# PCIE_CLK.net
KiCad netlist of a schematic drawn in Altium Designer
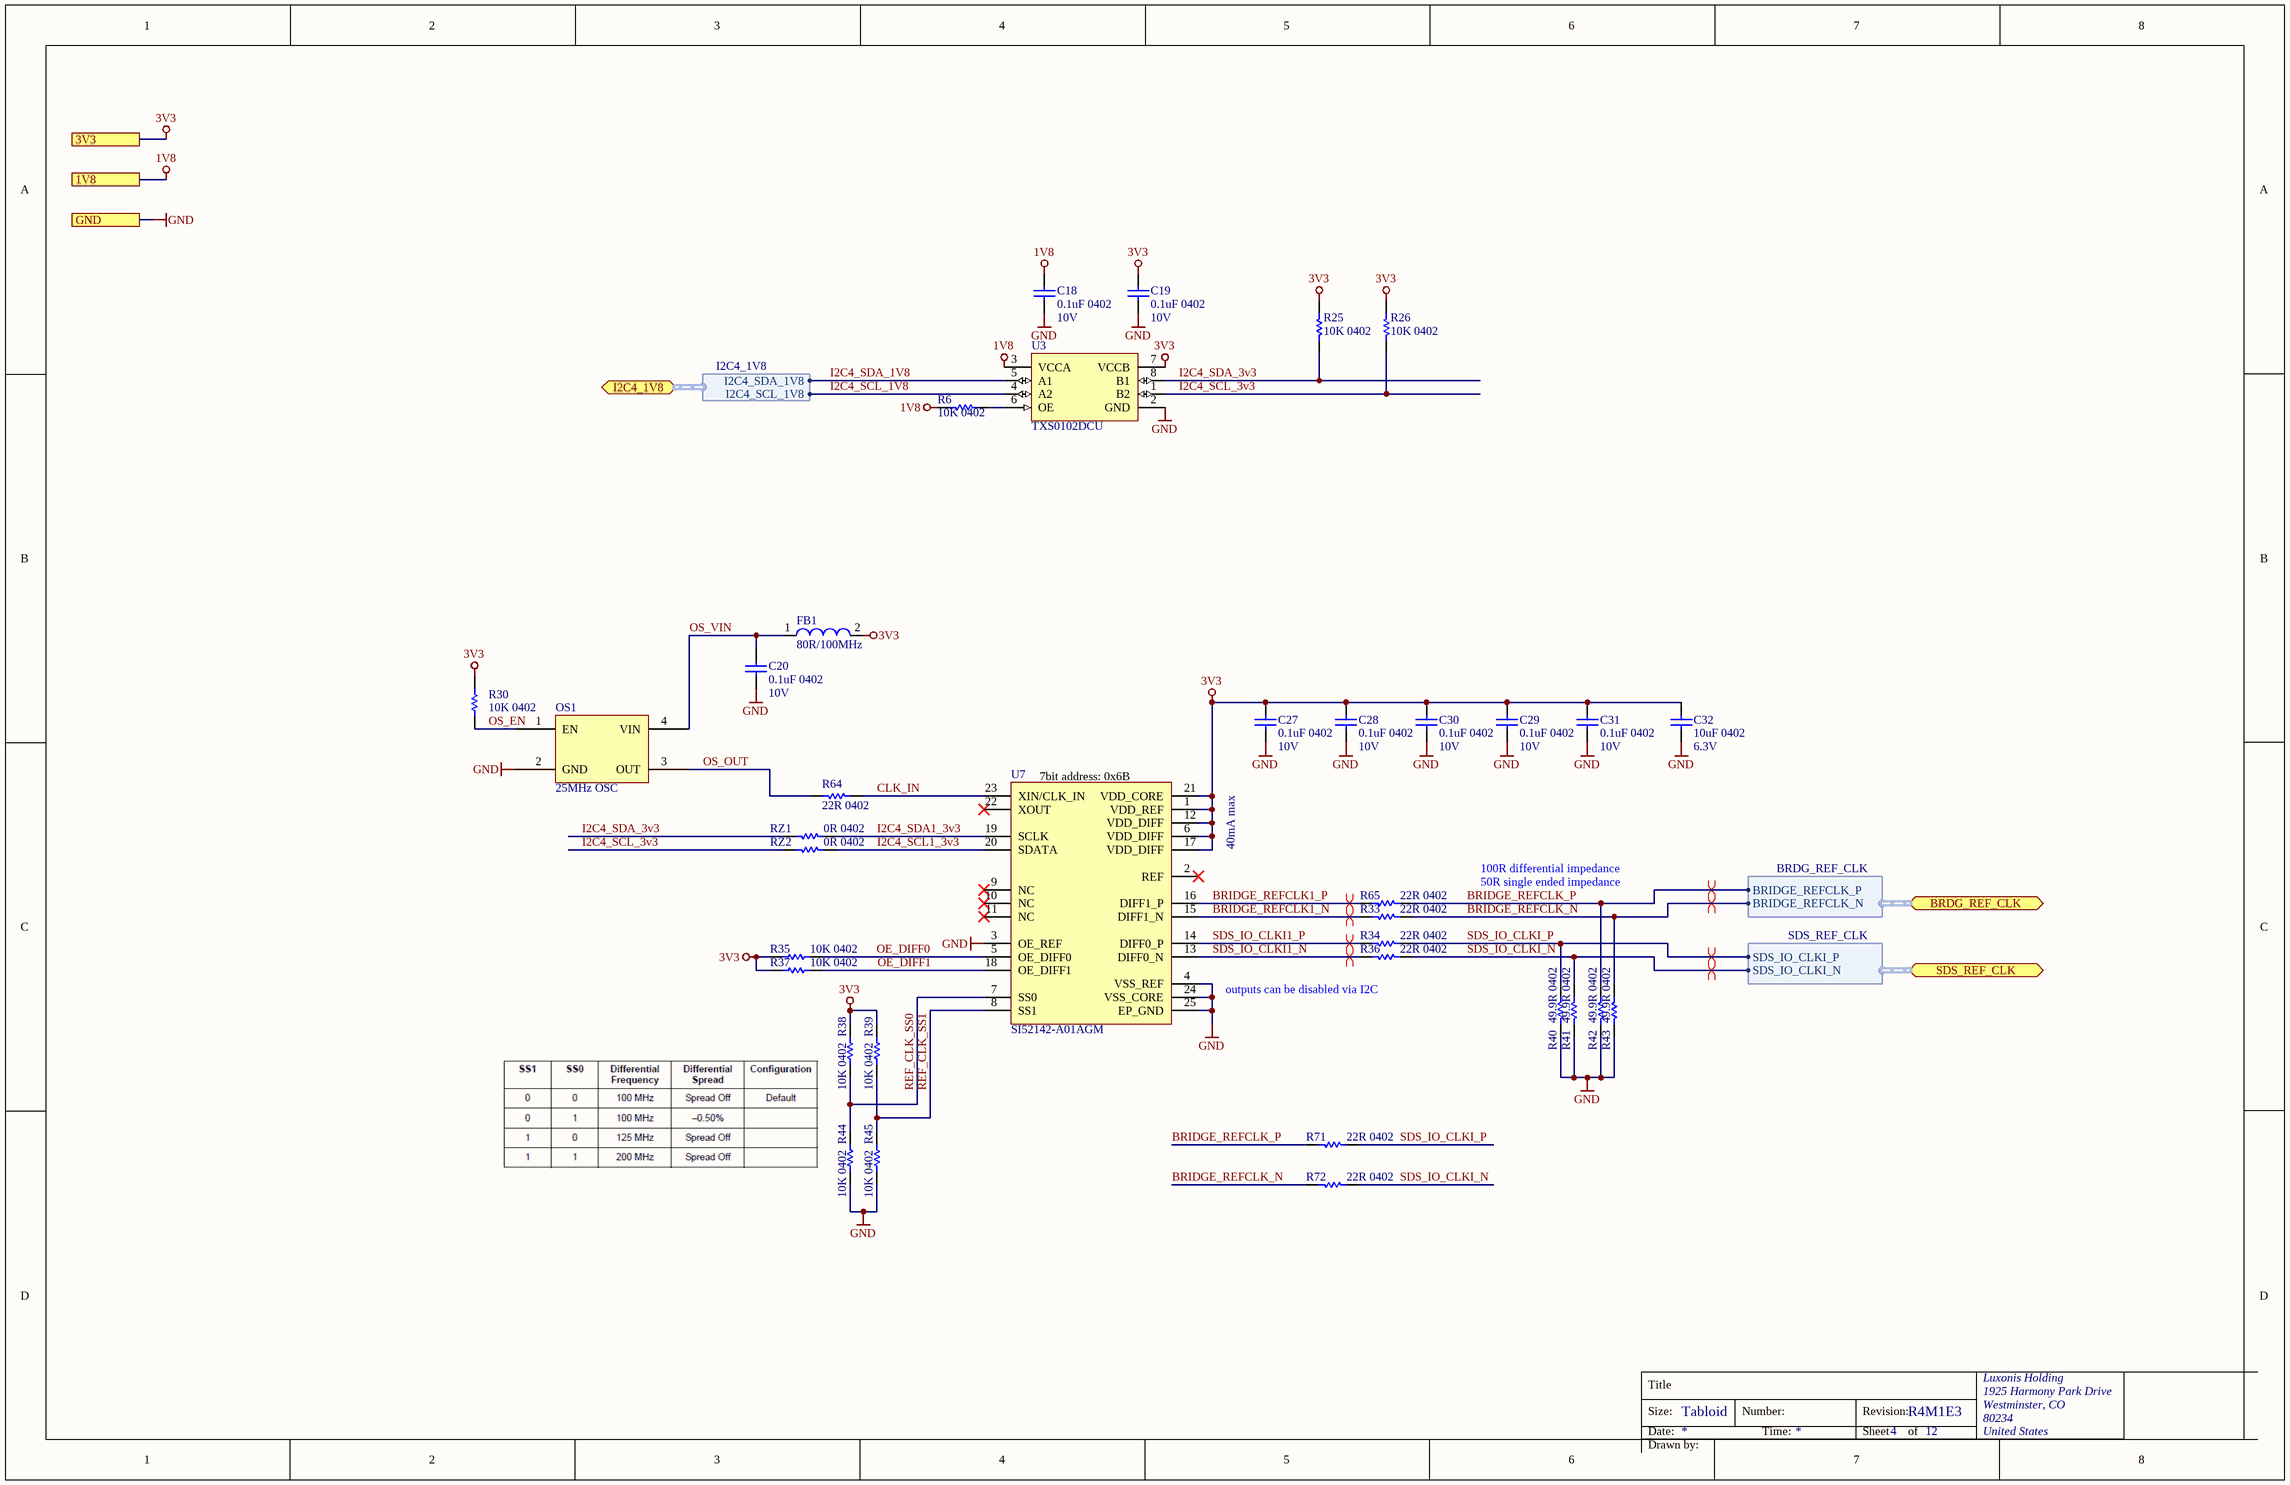
[diagram p0: PCIE_CLK.SchDoc]

(export (version "E")
  (design (tool "Eeschema 10.0.6"))
  (components
    (comp (ref "C18")
      (value "0.1uF 0402")
      (footprint "CAP_Altium_Vault_Generic:CAPC0402(1005)70_N")
      (description "CAP CER 0.1UF 10V X7R 0402 5%")
      (fields (field (name "TOLERANCE") "5%") (field (name "VOLTAGE RATING") "10V"))
      (libsource (lib "LuxonisMaster") (part "GRM155R71A104JA01D"))
    )
    (comp (ref "C19")
      (value "0.1uF 0402")
      (footprint "CAP_Altium_Vault_Generic:CAPC0402(1005)70_N")
      (description "CAP CER 0.1UF 10V X7R 0402 5%")
      (fields (field (name "TOLERANCE") "5%") (field (name "VOLTAGE RATING") "10V"))
      (libsource (lib "LuxonisMaster") (part "GRM155R71A104JA01D"))
    )
    (comp (ref "C20")
      (value "0.1uF 0402")
      (footprint "CAP_Altium_Vault_Generic:CAPC0402(1005)70_N")
      (description "CAP CER 0.1UF 10V X7R 0402 5%")
      (fields (field (name "TOLERANCE") "5%") (field (name "VOLTAGE RATING") "10V"))
      (libsource (lib "LuxonisMaster") (part "GRM155R71A104JA01D"))
    )
    (comp (ref "C27")
      (value "0.1uF 0402")
      (footprint "CAP_Altium_Vault_Generic:CAPC0402(1005)70_N")
      (description "CAP CER 0.1UF 10V X7R 0402 5%")
      (fields (field (name "TOLERANCE") "5%") (field (name "VOLTAGE RATING") "10V"))
      (libsource (lib "LuxonisMaster") (part "GRM155R71A104JA01D"))
    )
    (comp (ref "C28")
      (value "0.1uF 0402")
      (footprint "CAP_Altium_Vault_Generic:CAPC0402(1005)70_N")
      (description "CAP CER 0.1UF 10V X7R 0402 5%")
      (fields (field (name "TOLERANCE") "5%") (field (name "VOLTAGE RATING") "10V"))
      (libsource (lib "LuxonisMaster") (part "GRM155R71A104JA01D"))
    )
    (comp (ref "C29")
      (value "0.1uF 0402")
      (footprint "CAP_Altium_Vault_Generic:CAPC0402(1005)70_N")
      (description "CAP CER 0.1UF 10V X7R 0402 5%")
      (fields (field (name "TOLERANCE") "5%") (field (name "VOLTAGE RATING") "10V"))
      (libsource (lib "LuxonisMaster") (part "GRM155R71A104JA01D"))
    )
    (comp (ref "C30")
      (value "0.1uF 0402")
      (footprint "CAP_Altium_Vault_Generic:CAPC0402(1005)70_N")
      (description "CAP CER 0.1UF 10V X7R 0402 5%")
      (fields (field (name "TOLERANCE") "5%") (field (name "VOLTAGE RATING") "10V"))
      (libsource (lib "LuxonisMaster") (part "GRM155R71A104JA01D"))
    )
    (comp (ref "C31")
      (value "0.1uF 0402")
      (footprint "CAP_Altium_Vault_Generic:CAPC0402(1005)70_N")
      (description "CAP CER 0.1UF 10V X7R 0402 5%")
      (fields (field (name "TOLERANCE") "5%") (field (name "VOLTAGE RATING") "10V"))
      (libsource (lib "LuxonisMaster") (part "GRM155R71A104JA01D"))
    )
    (comp (ref "C32")
      (value "10uF 0402")
      (footprint "CAP_Altium_Vault_Generic:CAPC0402(1005)70_N")
      (description "CAP CER 10UF 6.3V X5R 0402 20%")
      (fields (field (name "TOLERANCE") "20%") (field (name "VOLTAGE RATING") "6.3V"))
      (libsource (lib "LuxonisMaster") (part "GRM155R60J106ME15D"))
    )
    (comp (ref "FB1")
      (value "80R/100MHz")
      (footprint "LuxonisMaster:BK1608HS800-T_N")
      (description "FERRITE BEAD 80 OHM 0603 1LN")
      (fields (field (name "TOLERANCE") "25%"))
      (libsource (lib "LuxonisMaster") (part "BK1608HS800-T"))
    )
    (comp (ref "OS1")
      (value "25MHz OSC")
      (footprint "BW2098POE:ASDMB-25.000MHZ-LC-T")
      (description "MEMS OSC XO 25.0000MHZ LVCMOS")
      (libsource (lib "BW2098POE") (part "ASDMB-25.000MHZ-LC-T"))
    )
    (comp (ref "R6")
      (value "10K 0402")
      (footprint "RES_Altium_Vault_Generic:RESC0402(1005)_N")
      (fields (field (name "TOLERANCE") "1%"))
      (libsource (lib "LuxonisMaster") (part "RC0402FR-1310KL"))
    )
    (comp (ref "R25")
      (value "10K 0402")
      (footprint "RES_Altium_Vault_Generic:RESC0402(1005)_N")
      (fields (field (name "TOLERANCE") "1%"))
      (libsource (lib "LuxonisMaster") (part "RC0402FR-1310KL"))
    )
    (comp (ref "R26")
      (value "10K 0402")
      (footprint "RES_Altium_Vault_Generic:RESC0402(1005)_N")
      (fields (field (name "TOLERANCE") "1%"))
      (libsource (lib "LuxonisMaster") (part "RC0402FR-1310KL"))
    )
    (comp (ref "R30")
      (value "10K 0402")
      (footprint "RES_Altium_Vault_Generic:RESC0402(1005)_N")
      (fields (field (name "TOLERANCE") "1%"))
      (libsource (lib "LuxonisMaster") (part "RC0402FR-1310KL"))
    )
    (comp (ref "R33")
      (value "22R 0402")
      (footprint "RES_Altium_Vault_Generic:RESC0402(1005)_L")
      (description "RES SMD 22 OHM 1% 1/16W 0402")
      (fields (field (name "TOLERANCE") "1%"))
      (libsource (lib "BW2098POE") (part "RC0402FR-0722RL"))
    )
    (comp (ref "R34")
      (value "22R 0402")
      (footprint "RES_Altium_Vault_Generic:RESC0402(1005)_L")
      (description "RES SMD 22 OHM 1% 1/16W 0402")
      (fields (field (name "TOLERANCE") "1%"))
      (libsource (lib "BW2098POE") (part "RC0402FR-0722RL"))
    )
    (comp (ref "R35")
      (value "10K 0402")
      (footprint "RES_Altium_Vault_Generic:RESC0402(1005)_N")
      (fields (field (name "TOLERANCE") "1%"))
      (libsource (lib "LuxonisMaster") (part "RC0402FR-1310KL"))
    )
    (comp (ref "R36")
      (value "22R 0402")
      (footprint "RES_Altium_Vault_Generic:RESC0402(1005)_L")
      (description "RES SMD 22 OHM 1% 1/16W 0402")
      (fields (field (name "TOLERANCE") "1%"))
      (libsource (lib "BW2098POE") (part "RC0402FR-0722RL"))
    )
    (comp (ref "R37")
      (value "10K 0402")
      (footprint "RES_Altium_Vault_Generic:RESC0402(1005)_N")
      (fields (field (name "TOLERANCE") "1%"))
      (libsource (lib "LuxonisMaster") (part "RC0402FR-1310KL"))
    )
    (comp (ref "R38")
      (value "10K 0402")
      (footprint "RES_Altium_Vault_Generic:RESC0402(1005)_N")
      (fields (field (name "TOLERANCE") "1%"))
      (libsource (lib "LuxonisMaster") (part "RC0402FR-1310KL"))
    )
    (comp (ref "R39")
      (value "10K 0402")
      (footprint "RES_Altium_Vault_Generic:RESC0402(1005)_N")
      (fields (field (name "TOLERANCE") "1%"))
      (libsource (lib "LuxonisMaster") (part "RC0402FR-1310KL"))
    )
    (comp (ref "R40")
      (value "49.9R 0402")
      (footprint "RES_Altium_Vault_Generic:RESC0402(1005)_L")
      (description "RES SMD 49.9 OHM 1% 1/16W 0402")
      (fields (field (name "TOLERANCE") "1%"))
      (libsource (lib "LuxonisMaster") (part "RC0402FR-0749R9L"))
    )
    (comp (ref "R41")
      (value "49.9R 0402")
      (footprint "RES_Altium_Vault_Generic:RESC0402(1005)_L")
      (description "RES SMD 49.9 OHM 1% 1/16W 0402")
      (fields (field (name "TOLERANCE") "1%"))
      (libsource (lib "LuxonisMaster") (part "RC0402FR-0749R9L"))
    )
    (comp (ref "R42")
      (value "49.9R 0402")
      (footprint "RES_Altium_Vault_Generic:RESC0402(1005)_L")
      (description "RES SMD 49.9 OHM 1% 1/16W 0402")
      (fields (field (name "TOLERANCE") "1%"))
      (libsource (lib "LuxonisMaster") (part "RC0402FR-0749R9L"))
    )
    (comp (ref "R43")
      (value "49.9R 0402")
      (footprint "RES_Altium_Vault_Generic:RESC0402(1005)_L")
      (description "RES SMD 49.9 OHM 1% 1/16W 0402")
      (fields (field (name "TOLERANCE") "1%"))
      (libsource (lib "LuxonisMaster") (part "RC0402FR-0749R9L"))
    )
    (comp (ref "R44")
      (value "10K 0402")
      (footprint "RES_Altium_Vault_Generic:RESC0402(1005)_N")
      (fields (field (name "TOLERANCE") "1%"))
      (libsource (lib "LuxonisMaster") (part "RC0402FR-1310KL"))
    )
    (comp (ref "R45")
      (value "10K 0402")
      (footprint "RES_Altium_Vault_Generic:RESC0402(1005)_N")
      (fields (field (name "TOLERANCE") "1%"))
      (libsource (lib "LuxonisMaster") (part "RC0402FR-1310KL"))
    )
    (comp (ref "R64")
      (value "22R 0402")
      (footprint "RES_Altium_Vault_Generic:RESC0402(1005)_N")
      (description "RES SMD 22 OHM 1% 1/16W 0402")
      (fields (field (name "TOLERANCE") "1%"))
      (libsource (lib "BW2098POE") (part "RC0402FR-0722RL"))
    )
    (comp (ref "R65")
      (value "22R 0402")
      (footprint "RES_Altium_Vault_Generic:RESC0402(1005)_L")
      (description "RES SMD 22 OHM 1% 1/16W 0402")
      (fields (field (name "TOLERANCE") "1%"))
      (libsource (lib "BW2098POE") (part "RC0402FR-0722RL"))
    )
    (comp (ref "R71")
      (value "22R 0402")
      (footprint "RES_Altium_Vault_Generic:RESC0402(1005)_L")
      (description "RES SMD 22 OHM 1% 1/16W 0402")
      (fields (field (name "TOLERANCE") "1%"))
      (libsource (lib "BW2098POE") (part "RC0402FR-0722RL"))
    )
    (comp (ref "R72")
      (value "22R 0402")
      (footprint "RES_Altium_Vault_Generic:RESC0402(1005)_L")
      (description "RES SMD 22 OHM 1% 1/16W 0402")
      (fields (field (name "TOLERANCE") "1%"))
      (libsource (lib "BW2098POE") (part "RC0402FR-0722RL"))
    )
    (comp (ref "RZ1")
      (value "0R 0402")
      (footprint "RES_Altium_Vault_Generic:RESC0402(1005)_N")
      (description "RES SMD 0 OHM JUMPER 1/16W 0402")
      (fields (field (name "TOLERANCE") "5%"))
      (libsource (lib "LuxonisMaster") (part "CRCW04020000Z0ED"))
    )
    (comp (ref "RZ2")
      (value "0R 0402")
      (footprint "RES_Altium_Vault_Generic:RESC0402(1005)_N")
      (description "RES SMD 0 OHM JUMPER 1/16W 0402")
      (fields (field (name "TOLERANCE") "5%"))
      (libsource (lib "LuxonisMaster") (part "CRCW04020000Z0ED"))
    )
    (comp (ref "U3")
      (value "TXS0102DCU")
      (footprint "BW2098POE:TXS0102DCUR")
      (description "TEXAS INSTRUMENTS - TXS0102DCUR - IC, TRANSLATOR, 2 BIT, BI, US-8")
      (libsource (lib "BW2098POE") (part "TXS0102DCUR"))
    )
    (comp (ref "U7")
      (value "SI52142-A01AGM")
      (footprint "BW2098POE:SI52142-A01AGM")
      (description "IC CLK GENERATOR 200MHZ 24QFN")
      (libsource (lib "BW2098POE") (part "SI52142-A01AGM"))
    )
  )
  (nets
    (net (code "4") (name "/BRIDGE_REFCLK1_N") (class "Default")
      (node (ref "R33") (pin "2") (pinfunction "2_2") (pintype "passive"))
      (node (ref "U7") (pin "15") (pinfunction "DIFF1_N_15") (pintype "passive"))
    )
    (net (code "5") (name "/BRIDGE_REFCLK1_P") (class "Default")
      (node (ref "R65") (pin "2") (pinfunction "2_2") (pintype "passive"))
      (node (ref "U7") (pin "16") (pinfunction "DIFF1_P_16") (pintype "passive"))
    )
    (net (code "6") (name "/BRIDGE_REFCLK_N") (class "Default")
      (node (ref "R33") (pin "1") (pinfunction "1_1") (pintype "passive"))
      (node (ref "R43") (pin "2") (pinfunction "2_2") (pintype "passive"))
      (node (ref "R72") (pin "2") (pinfunction "2_2") (pintype "passive"))
    )
    (net (code "7") (name "/BRIDGE_REFCLK_P") (class "Default")
      (node (ref "R42") (pin "2") (pinfunction "2_2") (pintype "passive"))
      (node (ref "R65") (pin "1") (pinfunction "1_1") (pintype "passive"))
      (node (ref "R71") (pin "2") (pinfunction "2_2") (pintype "passive"))
    )
    (net (code "8") (name "/CLK_IN") (class "Default")
      (node (ref "R64") (pin "1") (pinfunction "1_1") (pintype "passive"))
      (node (ref "U7") (pin "23") (pinfunction "XIN/CLK_IN_23") (pintype "passive"))
    )
    (net (code "9") (name "/I2C4_SCL1_3v3") (class "Default")
      (node (ref "RZ2") (pin "2") (pinfunction "2_2") (pintype "passive"))
      (node (ref "U7") (pin "20") (pinfunction "SDATA_20") (pintype "passive"))
    )
    (net (code "10") (name "/I2C4_SCL_1V8") (class "Default")
      (node (ref "U3") (pin "4") (pinfunction "A2_4") (pintype "bidirectional"))
    )
    (net (code "11") (name "/I2C4_SCL_3v3") (class "Default")
      (node (ref "R26") (pin "2") (pinfunction "2_2") (pintype "passive"))
      (node (ref "RZ2") (pin "1") (pinfunction "1_1") (pintype "passive"))
      (node (ref "U3") (pin "1") (pinfunction "B2_1") (pintype "bidirectional"))
    )
    (net (code "12") (name "/I2C4_SDA1_3v3") (class "Default")
      (node (ref "RZ1") (pin "2") (pinfunction "2_2") (pintype "passive"))
      (node (ref "U7") (pin "19") (pinfunction "SCLK_19") (pintype "passive"))
    )
    (net (code "13") (name "/I2C4_SDA_1V8") (class "Default")
      (node (ref "U3") (pin "5") (pinfunction "A1_5") (pintype "bidirectional"))
    )
    (net (code "14") (name "/I2C4_SDA_3v3") (class "Default")
      (node (ref "R25") (pin "2") (pinfunction "2_2") (pintype "passive"))
      (node (ref "RZ1") (pin "1") (pinfunction "1_1") (pintype "passive"))
      (node (ref "U3") (pin "8") (pinfunction "B1_8") (pintype "bidirectional"))
    )
    (net (code "15") (name "/OE_DIFF0") (class "Default")
      (node (ref "R35") (pin "2") (pinfunction "2_2") (pintype "passive"))
      (node (ref "U7") (pin "5") (pinfunction "OE_DIFF0_5") (pintype "passive"))
    )
    (net (code "16") (name "/OE_DIFF1") (class "Default")
      (node (ref "R37") (pin "2") (pinfunction "2_2") (pintype "passive"))
      (node (ref "U7") (pin "18") (pinfunction "OE_DIFF1_18") (pintype "passive"))
    )
    (net (code "17") (name "/OS_EN") (class "Default")
      (node (ref "OS1") (pin "1") (pinfunction "EN_1") (pintype "passive"))
      (node (ref "R30") (pin "1") (pinfunction "1_1") (pintype "passive"))
    )
    (net (code "18") (name "/OS_OUT") (class "Default")
      (node (ref "OS1") (pin "3") (pinfunction "OUT_3") (pintype "passive"))
      (node (ref "R64") (pin "2") (pinfunction "2_2") (pintype "passive"))
    )
    (net (code "19") (name "/OS_VIN") (class "Default")
      (node (ref "C20") (pin "1") (pinfunction "1_1") (pintype "passive"))
      (node (ref "FB1") (pin "1") (pinfunction "1_1") (pintype "passive"))
      (node (ref "OS1") (pin "4") (pinfunction "VIN_4") (pintype "passive"))
    )
    (net (code "20") (name "/REF_CLK_SS0") (class "Default")
      (node (ref "R38") (pin "2") (pinfunction "2_2") (pintype "passive"))
      (node (ref "R44") (pin "1") (pinfunction "1_1") (pintype "passive"))
      (node (ref "U7") (pin "7") (pinfunction "SS0_7") (pintype "passive"))
    )
    (net (code "21") (name "/REF_CLK_SS1") (class "Default")
      (node (ref "R39") (pin "2") (pinfunction "2_2") (pintype "passive"))
      (node (ref "R45") (pin "1") (pinfunction "1_1") (pintype "passive"))
      (node (ref "U7") (pin "8") (pinfunction "SS1_8") (pintype "passive"))
    )
    (net (code "22") (name "/SDS_IO_CLKI1_N") (class "Default")
      (node (ref "R36") (pin "2") (pinfunction "2_2") (pintype "passive"))
      (node (ref "U7") (pin "13") (pinfunction "DIFF0_N_13") (pintype "passive"))
    )
    (net (code "23") (name "/SDS_IO_CLKI1_P") (class "Default")
      (node (ref "R34") (pin "2") (pinfunction "2_2") (pintype "passive"))
      (node (ref "U7") (pin "14") (pinfunction "DIFF0_P_14") (pintype "passive"))
    )
    (net (code "24") (name "/SDS_IO_CLKI_N") (class "Default")
      (node (ref "R36") (pin "1") (pinfunction "1_1") (pintype "passive"))
      (node (ref "R41") (pin "2") (pinfunction "2_2") (pintype "passive"))
      (node (ref "R72") (pin "1") (pinfunction "1_1") (pintype "passive"))
    )
    (net (code "25") (name "/SDS_IO_CLKI_P") (class "Default")
      (node (ref "R34") (pin "1") (pinfunction "1_1") (pintype "passive"))
      (node (ref "R40") (pin "1") (pinfunction "1_1") (pintype "passive"))
      (node (ref "R71") (pin "1") (pinfunction "1_1") (pintype "passive"))
    )
    (net (code "29") (name "1V8") (class "Default")
      (node (ref "C18") (pin "2") (pinfunction "2_2") (pintype "passive"))
      (node (ref "R6") (pin "2") (pinfunction "2_2") (pintype "passive"))
      (node (ref "U3") (pin "3") (pinfunction "VCCA_3") (pintype "power_in"))
    )
    (net (code "30") (name "3V3") (class "Default")
      (node (ref "C19") (pin "2") (pinfunction "2_2") (pintype "passive"))
      (node (ref "C27") (pin "1") (pinfunction "1_1") (pintype "passive"))
      (node (ref "C28") (pin "1") (pinfunction "1_1") (pintype "passive"))
      (node (ref "C29") (pin "1") (pinfunction "1_1") (pintype "passive"))
      (node (ref "C30") (pin "1") (pinfunction "1_1") (pintype "passive"))
      (node (ref "C31") (pin "1") (pinfunction "1_1") (pintype "passive"))
      (node (ref "C32") (pin "2") (pinfunction "2_2") (pintype "passive"))
      (node (ref "FB1") (pin "2") (pinfunction "2_2") (pintype "passive"))
      (node (ref "R25") (pin "1") (pinfunction "1_1") (pintype "passive"))
      (node (ref "R26") (pin "1") (pinfunction "1_1") (pintype "passive"))
      (node (ref "R30") (pin "2") (pinfunction "2_2") (pintype "passive"))
      (node (ref "R35") (pin "1") (pinfunction "1_1") (pintype "passive"))
      (node (ref "R37") (pin "1") (pinfunction "1_1") (pintype "passive"))
      (node (ref "R38") (pin "1") (pinfunction "1_1") (pintype "passive"))
      (node (ref "R39") (pin "1") (pinfunction "1_1") (pintype "passive"))
      (node (ref "U3") (pin "7") (pinfunction "VCCB_7") (pintype "power_in"))
      (node (ref "U7") (pin "1") (pinfunction "VDD_REF_1") (pintype "passive"))
      (node (ref "U7") (pin "12") (pinfunction "VDD_DIFF_12") (pintype "passive"))
      (node (ref "U7") (pin "17") (pinfunction "VDD_DIFF_17") (pintype "passive"))
      (node (ref "U7") (pin "21") (pinfunction "VDD_CORE_21") (pintype "passive"))
      (node (ref "U7") (pin "6") (pinfunction "VDD_DIFF_6") (pintype "passive"))
    )
    (net (code "31") (name "GND") (class "Default")
      (node (ref "C18") (pin "1") (pinfunction "1_1") (pintype "passive"))
      (node (ref "C19") (pin "1") (pinfunction "1_1") (pintype "passive"))
      (node (ref "C20") (pin "2") (pinfunction "2_2") (pintype "passive"))
      (node (ref "C27") (pin "2") (pinfunction "2_2") (pintype "passive"))
      (node (ref "C28") (pin "2") (pinfunction "2_2") (pintype "passive"))
      (node (ref "C29") (pin "2") (pinfunction "2_2") (pintype "passive"))
      (node (ref "C30") (pin "2") (pinfunction "2_2") (pintype "passive"))
      (node (ref "C31") (pin "2") (pinfunction "2_2") (pintype "passive"))
      (node (ref "C32") (pin "1") (pinfunction "1_1") (pintype "passive"))
      (node (ref "OS1") (pin "2") (pinfunction "GND_2") (pintype "passive"))
      (node (ref "R40") (pin "2") (pinfunction "2_2") (pintype "passive"))
      (node (ref "R41") (pin "1") (pinfunction "1_1") (pintype "passive"))
      (node (ref "R42") (pin "1") (pinfunction "1_1") (pintype "passive"))
      (node (ref "R43") (pin "1") (pinfunction "1_1") (pintype "passive"))
      (node (ref "R44") (pin "2") (pinfunction "2_2") (pintype "passive"))
      (node (ref "R45") (pin "2") (pinfunction "2_2") (pintype "passive"))
      (node (ref "U3") (pin "2") (pinfunction "GND_2") (pintype "power_in"))
      (node (ref "U7") (pin "24") (pinfunction "VSS_CORE_24") (pintype "passive"))
      (node (ref "U7") (pin "25") (pinfunction "EP_GND_25") (pintype "passive"))
      (node (ref "U7") (pin "3") (pinfunction "OE_REF_3") (pintype "passive"))
      (node (ref "U7") (pin "4") (pinfunction "VSS_REF_4") (pintype "passive"))
    )
    (net (code "32") (name "Net-(U3-OE)") (class "Default")
      (node (ref "R6") (pin "1") (pinfunction "1_1") (pintype "passive"))
      (node (ref "U3") (pin "6") (pinfunction "OE_6") (pintype "input"))
    )
    (net (code "33") (name "unconnected-(U7-NC-Pad9)") (class "Default")
      (node (ref "U7") (pin "9") (pinfunction "NC_9") (pintype "passive+no_connect"))
    )
    (net (code "34") (name "unconnected-(U7-NC-Pad10)") (class "Default")
      (node (ref "U7") (pin "10") (pinfunction "NC_10") (pintype "passive+no_connect"))
    )
    (net (code "35") (name "unconnected-(U7-NC-Pad11)") (class "Default")
      (node (ref "U7") (pin "11") (pinfunction "NC_11") (pintype "passive+no_connect"))
    )
    (net (code "36") (name "unconnected-(U7-REF-Pad2)") (class "Default")
      (node (ref "U7") (pin "2") (pinfunction "REF_2") (pintype "passive+no_connect"))
    )
    (net (code "37") (name "unconnected-(U7-XOUT-Pad22)") (class "Default")
      (node (ref "U7") (pin "22") (pinfunction "XOUT_22") (pintype "passive+no_connect"))
    )
  )
)
